# MCU_Module.net
KiCad netlist of a schematic drawn in Altium Designer
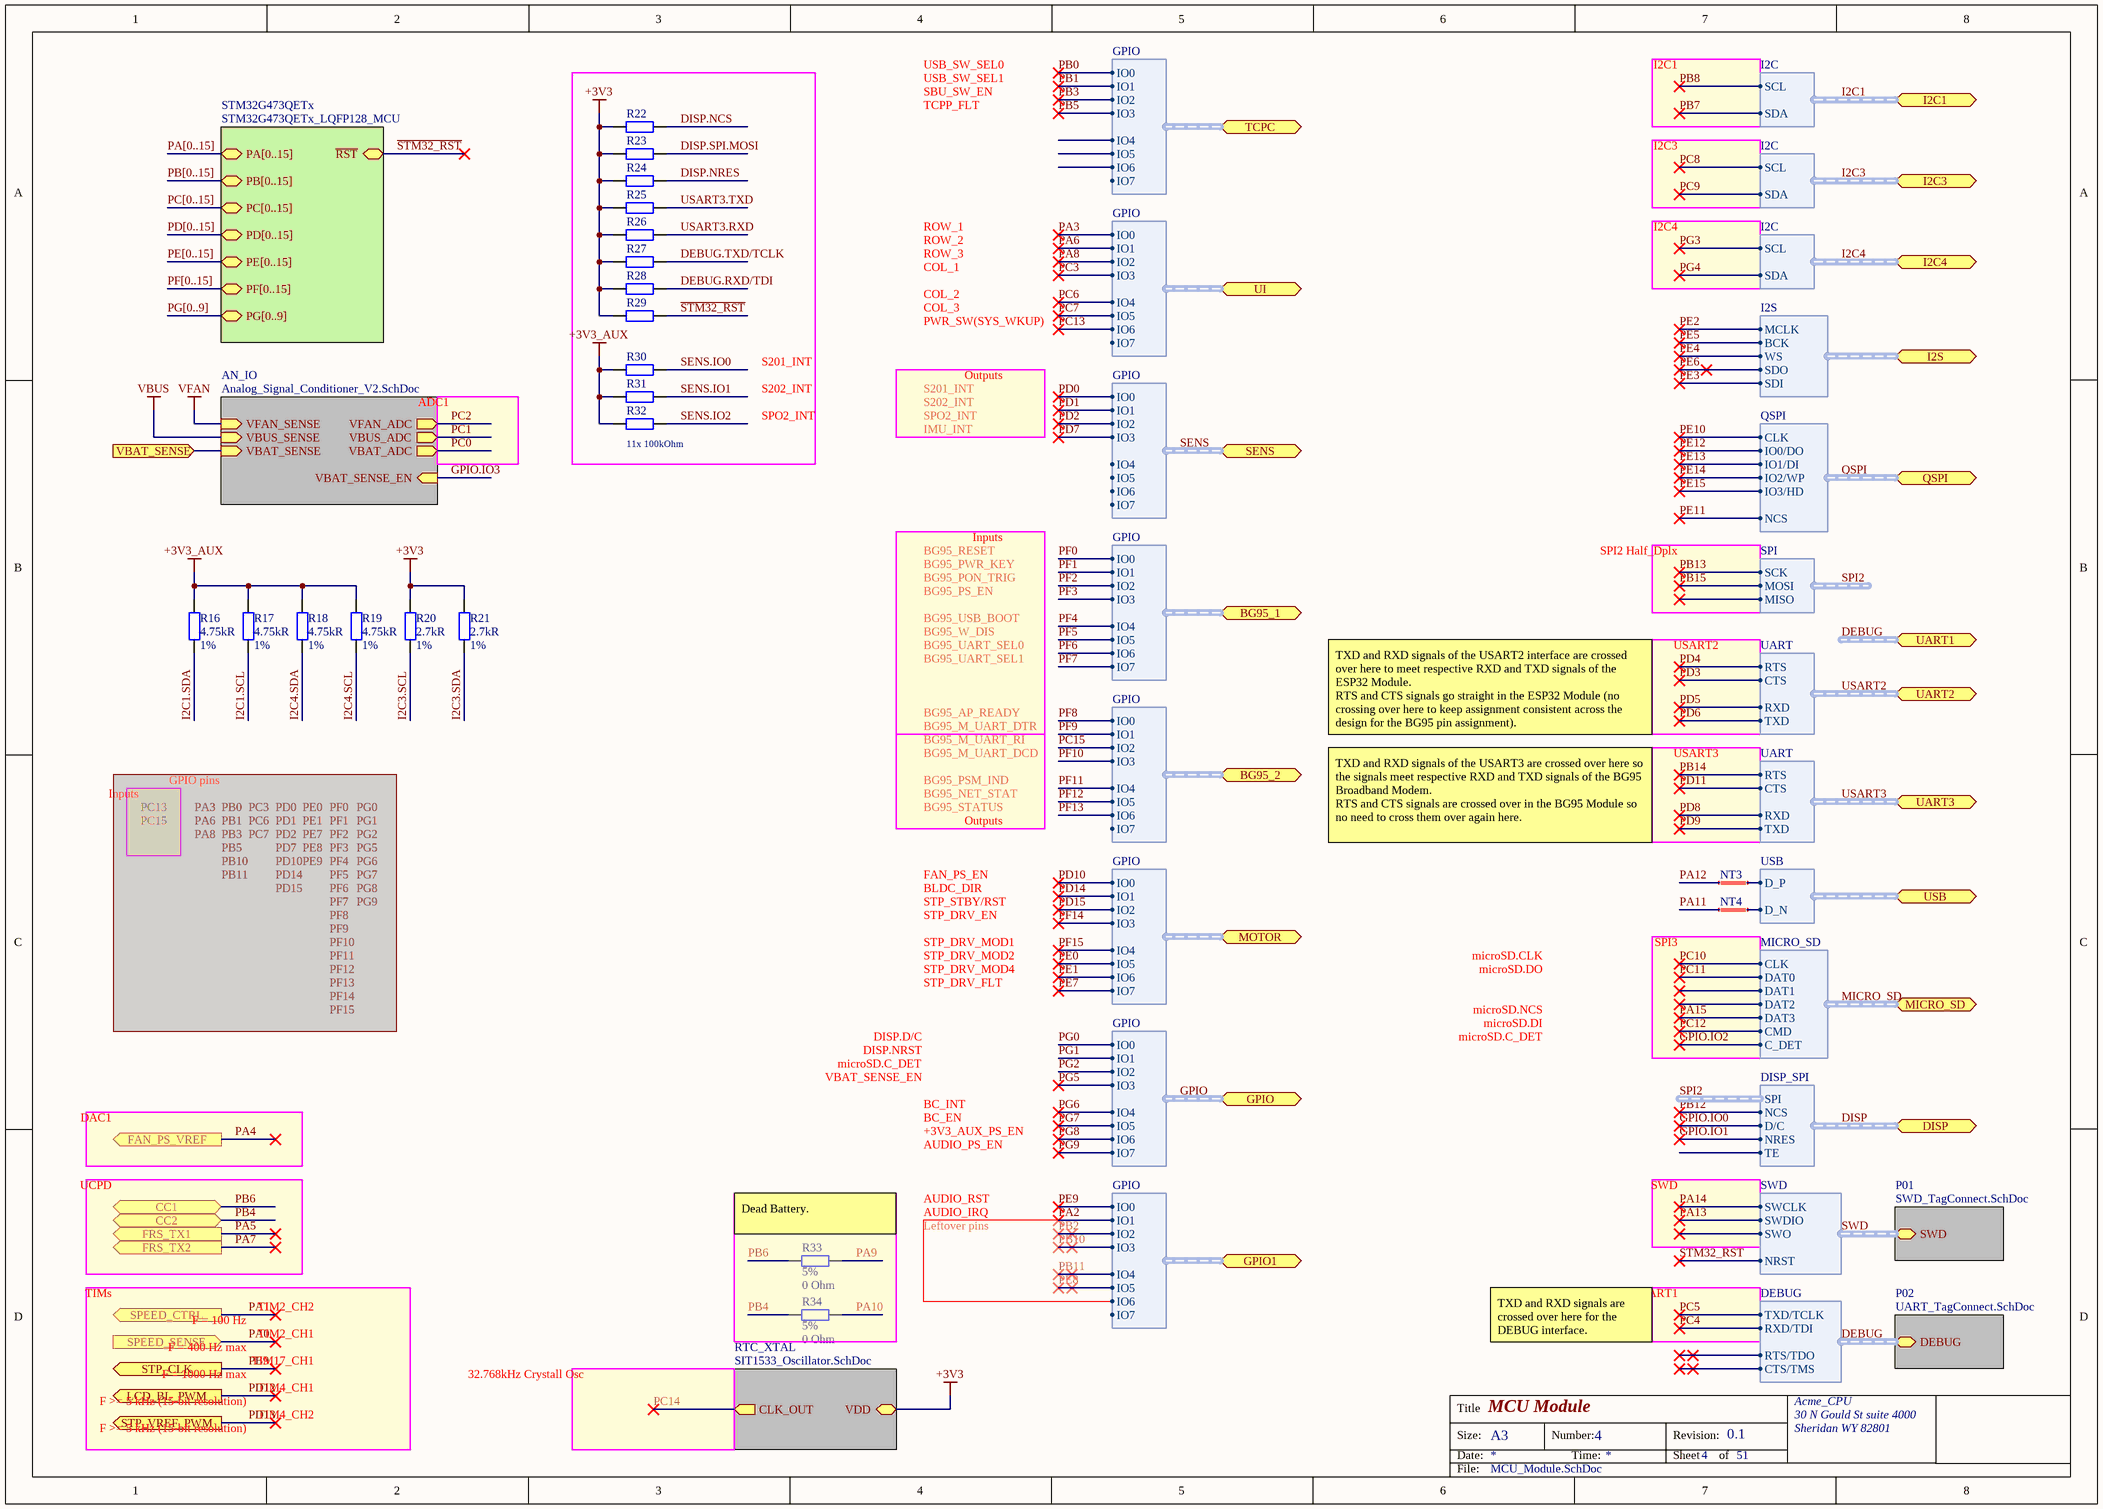
[diagram p0: MCU_Module.SchDoc]

(export (version "E")
  (design (tool "Eeschema 10.0.6"))
  (components
    (comp (ref "NT3")
      (value "Net Tie")
      (footprint "Net Tie 6x30mil")
      (libsource (lib "BLDC_Motor_Driver") (part "Net Tie Line"))
    )
    (comp (ref "NT4")
      (value "Net Tie")
      (footprint "Net Tie 6x30mil")
      (libsource (lib "BLDC_Motor_Driver") (part "Net Tie Line"))
    )
    (comp (ref "R16")
      (value "RES SMD 4.75K OHM 1% 1/16W 0402")
      (footprint "R0402")
      (description "4.75 kOhms ±1% 0.063W, 1/16W Chip Resistor 0402 (1005 Metric) Moisture Resistant Thick Film")
      (fields
        (field (name "MANUFACTURER") "Yageo")
        (field (name "MANUFACTURER PART NUMBER") "RC0402FR-074K75P")
        (field (name "RESISTANCE") "4.75kR")
        (field (name "TOLERANCE") "1%")
      )
      (libsource (lib "resistors_smd") (part "RES SMD 4.75K OHM 1% 1/16W 0402"))
    )
    (comp (ref "R17")
      (value "RES SMD 4.75K OHM 1% 1/16W 0402")
      (footprint "R0402")
      (description "4.75 kOhms ±1% 0.063W, 1/16W Chip Resistor 0402 (1005 Metric) Moisture Resistant Thick Film")
      (fields
        (field (name "MANUFACTURER") "Yageo")
        (field (name "MANUFACTURER PART NUMBER") "RC0402FR-074K75P")
        (field (name "RESISTANCE") "4.75kR")
        (field (name "TOLERANCE") "1%")
      )
      (libsource (lib "resistors_smd") (part "RES SMD 4.75K OHM 1% 1/16W 0402"))
    )
    (comp (ref "R18")
      (value "RES SMD 4.75K OHM 1% 1/16W 0402")
      (footprint "R0402")
      (description "4.75 kOhms ±1% 0.063W, 1/16W Chip Resistor 0402 (1005 Metric) Moisture Resistant Thick Film")
      (fields
        (field (name "MANUFACTURER") "Yageo")
        (field (name "MANUFACTURER PART NUMBER") "RC0402FR-074K75P")
        (field (name "RESISTANCE") "4.75kR")
        (field (name "TOLERANCE") "1%")
      )
      (libsource (lib "resistors_smd") (part "RES SMD 4.75K OHM 1% 1/16W 0402"))
    )
    (comp (ref "R19")
      (value "RES SMD 4.75K OHM 1% 1/16W 0402")
      (footprint "R0402")
      (description "4.75 kOhms ±1% 0.063W, 1/16W Chip Resistor 0402 (1005 Metric) Moisture Resistant Thick Film")
      (fields
        (field (name "MANUFACTURER") "Yageo")
        (field (name "MANUFACTURER PART NUMBER") "RC0402FR-074K75P")
        (field (name "RESISTANCE") "4.75kR")
        (field (name "TOLERANCE") "1%")
      )
      (libsource (lib "resistors_smd") (part "RES SMD 4.75K OHM 1% 1/16W 0402"))
    )
    (comp (ref "R20")
      (value "RES SMD 2.7K OHM 1% 1/16W 0402")
      (footprint "R0402")
      (description "2.7 kOhms ±1% 0.063W, 1/16W Chip Resistor 0402 (1005 Metric) Moisture Resistant Thick Film")
      (fields
        (field (name "MANUFACTURER") "Yageo")
        (field (name "MANUFACTURER PART NUMBER") "RC0402FR-072K7L")
        (field (name "RESISTANCE") "2.7kR")
        (field (name "TOLERANCE") "1%")
      )
      (libsource (lib "resistors_smd") (part "RES SMD 2.7K OHM 1% 1/16W 0402"))
    )
    (comp (ref "R21")
      (value "RES SMD 2.7K OHM 1% 1/16W 0402")
      (footprint "R0402")
      (description "2.7 kOhms ±1% 0.063W, 1/16W Chip Resistor 0402 (1005 Metric) Moisture Resistant Thick Film")
      (fields
        (field (name "MANUFACTURER") "Yageo")
        (field (name "MANUFACTURER PART NUMBER") "RC0402FR-072K7L")
        (field (name "RESISTANCE") "2.7kR")
        (field (name "TOLERANCE") "1%")
      )
      (libsource (lib "resistors_smd") (part "RES SMD 2.7K OHM 1% 1/16W 0402"))
    )
    (comp (ref "R22")
      (value "RES SMD 100K OHM 1% 1/16W 0402")
      (footprint "R0402")
      (description "100 kOhms ±1% 0.063W, 1/16W Chip Resistor 0402 (1005 Metric) Moisture Resistant Thick Film")
      (fields
        (field (name "MANUFACTURER") "Yageo")
        (field (name "MANUFACTURER PART NUMBER") "RC0402FR-07100KL")
      )
      (libsource (lib "resistors_smd") (part "RES SMD 100K OHM 1% 1/16W 0402"))
    )
    (comp (ref "R23")
      (value "RES SMD 100K OHM 1% 1/16W 0402")
      (footprint "R0402")
      (description "100 kOhms ±1% 0.063W, 1/16W Chip Resistor 0402 (1005 Metric) Moisture Resistant Thick Film")
      (fields
        (field (name "MANUFACTURER") "Yageo")
        (field (name "MANUFACTURER PART NUMBER") "RC0402FR-07100KL")
      )
      (libsource (lib "resistors_smd") (part "RES SMD 100K OHM 1% 1/16W 0402"))
    )
    (comp (ref "R24")
      (value "RES SMD 100K OHM 1% 1/16W 0402")
      (footprint "R0402")
      (description "100 kOhms ±1% 0.063W, 1/16W Chip Resistor 0402 (1005 Metric) Moisture Resistant Thick Film")
      (fields
        (field (name "MANUFACTURER") "Yageo")
        (field (name "MANUFACTURER PART NUMBER") "RC0402FR-07100KL")
      )
      (libsource (lib "resistors_smd") (part "RES SMD 100K OHM 1% 1/16W 0402"))
    )
    (comp (ref "R25")
      (value "RES SMD 100K OHM 1% 1/16W 0402")
      (footprint "R0402")
      (description "100 kOhms ±1% 0.063W, 1/16W Chip Resistor 0402 (1005 Metric) Moisture Resistant Thick Film")
      (fields
        (field (name "MANUFACTURER") "Yageo")
        (field (name "MANUFACTURER PART NUMBER") "RC0402FR-07100KL")
      )
      (libsource (lib "resistors_smd") (part "RES SMD 100K OHM 1% 1/16W 0402"))
    )
    (comp (ref "R26")
      (value "RES SMD 100K OHM 1% 1/16W 0402")
      (footprint "R0402")
      (description "100 kOhms ±1% 0.063W, 1/16W Chip Resistor 0402 (1005 Metric) Moisture Resistant Thick Film")
      (fields
        (field (name "MANUFACTURER") "Yageo")
        (field (name "MANUFACTURER PART NUMBER") "RC0402FR-07100KL")
      )
      (libsource (lib "resistors_smd") (part "RES SMD 100K OHM 1% 1/16W 0402"))
    )
    (comp (ref "R27")
      (value "RES SMD 100K OHM 1% 1/16W 0402")
      (footprint "R0402")
      (description "100 kOhms ±1% 0.063W, 1/16W Chip Resistor 0402 (1005 Metric) Moisture Resistant Thick Film")
      (fields
        (field (name "MANUFACTURER") "Yageo")
        (field (name "MANUFACTURER PART NUMBER") "RC0402FR-07100KL")
      )
      (libsource (lib "resistors_smd") (part "RES SMD 100K OHM 1% 1/16W 0402"))
    )
    (comp (ref "R28")
      (value "RES SMD 100K OHM 1% 1/16W 0402")
      (footprint "R0402")
      (description "100 kOhms ±1% 0.063W, 1/16W Chip Resistor 0402 (1005 Metric) Moisture Resistant Thick Film")
      (fields
        (field (name "MANUFACTURER") "Yageo")
        (field (name "MANUFACTURER PART NUMBER") "RC0402FR-07100KL")
      )
      (libsource (lib "resistors_smd") (part "RES SMD 100K OHM 1% 1/16W 0402"))
    )
    (comp (ref "R29")
      (value "RES SMD 100K OHM 1% 1/16W 0402")
      (footprint "R0402")
      (description "100 kOhms ±1% 0.063W, 1/16W Chip Resistor 0402 (1005 Metric) Moisture Resistant Thick Film")
      (fields
        (field (name "MANUFACTURER") "Yageo")
        (field (name "MANUFACTURER PART NUMBER") "RC0402FR-07100KL")
      )
      (libsource (lib "resistors_smd") (part "RES SMD 100K OHM 1% 1/16W 0402"))
    )
    (comp (ref "R30")
      (value "RES SMD 100K OHM 1% 1/16W 0402")
      (footprint "R0402")
      (description "100 kOhms ±1% 0.063W, 1/16W Chip Resistor 0402 (1005 Metric) Moisture Resistant Thick Film")
      (fields
        (field (name "MANUFACTURER") "Yageo")
        (field (name "MANUFACTURER PART NUMBER") "RC0402FR-07100KL")
      )
      (libsource (lib "resistors_smd") (part "RES SMD 100K OHM 1% 1/16W 0402"))
    )
    (comp (ref "R31")
      (value "RES SMD 100K OHM 1% 1/16W 0402")
      (footprint "R0402")
      (description "100 kOhms ±1% 0.063W, 1/16W Chip Resistor 0402 (1005 Metric) Moisture Resistant Thick Film")
      (fields
        (field (name "MANUFACTURER") "Yageo")
        (field (name "MANUFACTURER PART NUMBER") "RC0402FR-07100KL")
      )
      (libsource (lib "resistors_smd") (part "RES SMD 100K OHM 1% 1/16W 0402"))
    )
    (comp (ref "R32")
      (value "RES SMD 100K OHM 1% 1/16W 0402")
      (footprint "R0402")
      (description "100 kOhms ±1% 0.063W, 1/16W Chip Resistor 0402 (1005 Metric) Moisture Resistant Thick Film")
      (fields
        (field (name "MANUFACTURER") "Yageo")
        (field (name "MANUFACTURER PART NUMBER") "RC0402FR-07100KL")
      )
      (libsource (lib "resistors_smd") (part "RES SMD 100K OHM 1% 1/16W 0402"))
    )
    (comp (ref "R33")
      (value "RES SMD 0 OHM JUMPER 1/16W 0402")
      (footprint "R0402")
      (description "0 Ohms Jumper 0.063W, 1/16W Chip Resistor 0402 (1005 Metric) Moisture Resistant Thick Film")
      (fields
        (field (name "MANUFACTURER") "Yageo")
        (field (name "MANUFACTURER PART NUMBER") "RC0402JR-070RL")
        (field (name "TOLERANCE") "5%")
        (field (name "RESISTANCE") "0 Ohm")
      )
      (libsource (lib "resistors_smd") (part "RES SMD 0 OHM JUMPER 1/16W 0402"))
    )
    (comp (ref "R34")
      (value "RES SMD 0 OHM JUMPER 1/16W 0402")
      (footprint "R0402")
      (description "0 Ohms Jumper 0.063W, 1/16W Chip Resistor 0402 (1005 Metric) Moisture Resistant Thick Film")
      (fields
        (field (name "MANUFACTURER") "Yageo")
        (field (name "MANUFACTURER PART NUMBER") "RC0402JR-070RL")
        (field (name "TOLERANCE") "5%")
        (field (name "RESISTANCE") "0 Ohm")
      )
      (libsource (lib "resistors_smd") (part "RES SMD 0 OHM JUMPER 1/16W 0402"))
    )
  )
  (nets
    (net (code "19") (name "+3V3") (class "Default")
      (node (ref "R20") (pin "2") (pinfunction "2_2") (pintype "passive"))
      (node (ref "R21") (pin "2") (pinfunction "2_2") (pintype "passive"))
      (node (ref "R22") (pin "1") (pinfunction "1_1") (pintype "passive"))
      (node (ref "R23") (pin "1") (pinfunction "1_1") (pintype "passive"))
      (node (ref "R24") (pin "1") (pinfunction "1_1") (pintype "passive"))
      (node (ref "R25") (pin "1") (pinfunction "1_1") (pintype "passive"))
      (node (ref "R26") (pin "1") (pinfunction "1_1") (pintype "passive"))
      (node (ref "R27") (pin "1") (pinfunction "1_1") (pintype "passive"))
      (node (ref "R28") (pin "1") (pinfunction "1_1") (pintype "passive"))
      (node (ref "R29") (pin "1") (pinfunction "1_1") (pintype "passive"))
    )
    (net (code "20") (name "+3V3_AUX") (class "Default")
      (node (ref "R16") (pin "2") (pinfunction "2_2") (pintype "passive"))
      (node (ref "R17") (pin "2") (pinfunction "2_2") (pintype "passive"))
      (node (ref "R18") (pin "2") (pinfunction "2_2") (pintype "passive"))
      (node (ref "R19") (pin "2") (pinfunction "2_2") (pintype "passive"))
      (node (ref "R30") (pin "1") (pinfunction "1_1") (pintype "passive"))
      (node (ref "R31") (pin "1") (pinfunction "1_1") (pintype "passive"))
      (node (ref "R32") (pin "1") (pinfunction "1_1") (pintype "passive"))
    )
    (net (code "24") (name "/DEBUG.RXD{slash}TDI") (class "Default")
      (node (ref "R28") (pin "2") (pinfunction "2_2") (pintype "passive"))
    )
    (net (code "25") (name "/DEBUG.TXD{slash}TCLK") (class "Default")
      (node (ref "R27") (pin "2") (pinfunction "2_2") (pintype "passive"))
    )
    (net (code "27") (name "/DISP.NCS") (class "Default")
      (node (ref "R22") (pin "2") (pinfunction "2_2") (pintype "passive"))
    )
    (net (code "28") (name "/DISP.NRES") (class "Default")
      (node (ref "R24") (pin "2") (pinfunction "2_2") (pintype "passive"))
    )
    (net (code "29") (name "/DISP.SPI.MOSI") (class "Default")
      (node (ref "R23") (pin "2") (pinfunction "2_2") (pintype "passive"))
    )
    (net (code "30") (name "/D_N") (class "Default") (node (ref "NT4") (pin "2") (pintype "passive")))
    (net (code "31") (name "/D_P") (class "Default") (node (ref "NT3") (pin "2") (pintype "passive")))
    (net (code "37") (name "/I2C1.SCL") (class "Default")
      (node (ref "R17") (pin "1") (pinfunction "1_1") (pintype "passive"))
    )
    (net (code "38") (name "/I2C1.SDA") (class "Default")
      (node (ref "R16") (pin "1") (pinfunction "1_1") (pintype "passive"))
    )
    (net (code "40") (name "/I2C3.SCL") (class "Default")
      (node (ref "R20") (pin "1") (pinfunction "1_1") (pintype "passive"))
    )
    (net (code "41") (name "/I2C3.SDA") (class "Default")
      (node (ref "R21") (pin "1") (pinfunction "1_1") (pintype "passive"))
    )
    (net (code "43") (name "/I2C4.SCL") (class "Default")
      (node (ref "R19") (pin "1") (pinfunction "1_1") (pintype "passive"))
    )
    (net (code "44") (name "/I2C4.SDA") (class "Default")
      (node (ref "R18") (pin "1") (pinfunction "1_1") (pintype "passive"))
    )
    (net (code "57") (name "/PA9") (class "Default")
      (node (ref "R33") (pin "2") (pinfunction "2_2") (pintype "passive"))
    )
    (net (code "58") (name "/PA10") (class "Default")
      (node (ref "R34") (pin "2") (pinfunction "2_2") (pintype "passive"))
    )
    (net (code "59") (name "/PA11") (class "Default") (node (ref "NT4") (pin "1") (pintype "passive")))
    (net (code "60") (name "/PA12") (class "Default") (node (ref "NT3") (pin "1") (pintype "passive")))
    (net (code "69") (name "/PB4") (class "Default")
      (node (ref "R34") (pin "1") (pinfunction "1_1") (pintype "passive"))
    )
    (net (code "71") (name "/PB6") (class "Default")
      (node (ref "R33") (pin "1") (pinfunction "1_1") (pintype "passive"))
    )
    (net (code "163") (name "/SENS.IO0") (class "Default")
      (node (ref "R30") (pin "2") (pinfunction "2_2") (pintype "passive"))
    )
    (net (code "164") (name "/SENS.IO1") (class "Default")
      (node (ref "R31") (pin "2") (pinfunction "2_2") (pintype "passive"))
    )
    (net (code "165") (name "/SENS.IO2") (class "Default")
      (node (ref "R32") (pin "2") (pinfunction "2_2") (pintype "passive"))
    )
    (net (code "169") (name "/STM32_RST") (class "Default")
      (node (ref "R29") (pin "2") (pinfunction "2_2") (pintype "passive+no_connect"))
    )
    (net (code "174") (name "/USART3.RXD") (class "Default")
      (node (ref "R26") (pin "2") (pinfunction "2_2") (pintype "passive"))
    )
    (net (code "175") (name "/USART3.TXD") (class "Default")
      (node (ref "R25") (pin "2") (pinfunction "2_2") (pintype "passive"))
    )
  )
)
